# Temp-sensor-RS485.net
KiCad netlist of a schematic drawn in EAGLE
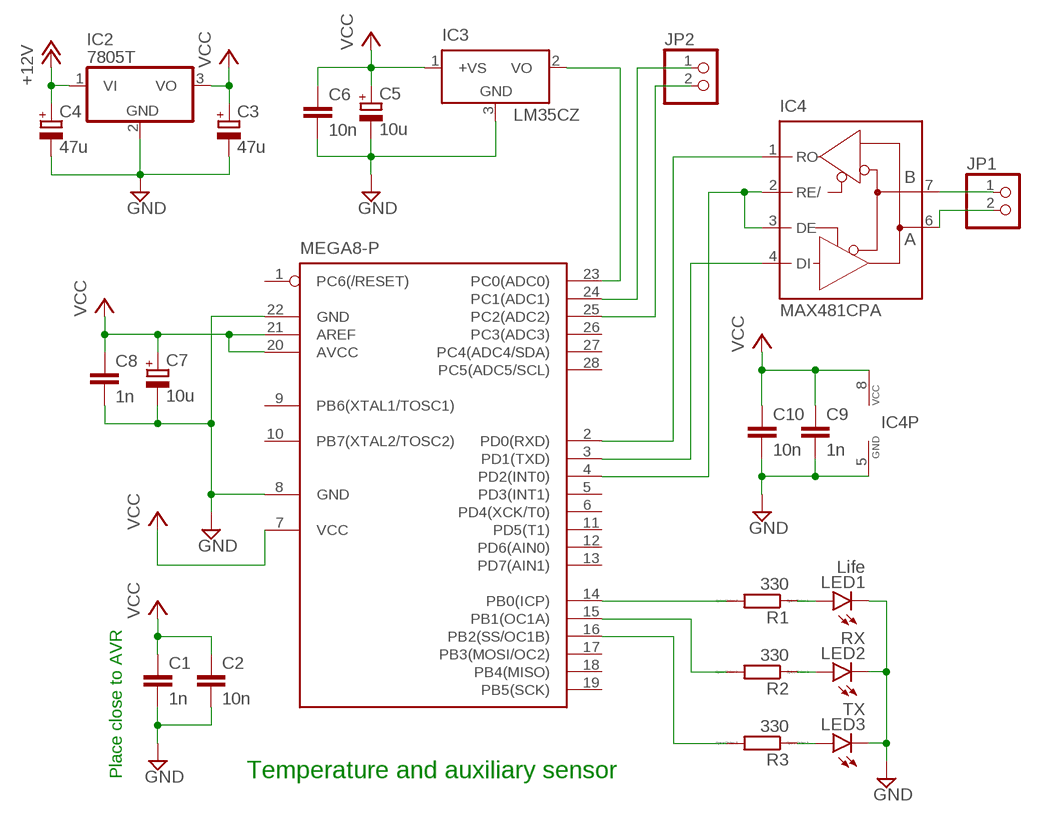
[diagram p0: schematic, sheet 1]

(export (version "E")
  (design (tool "Eeschema 10.0.6"))
  (components
    (comp (ref "C1")
      (value "1n")
      (footprint "eagle-import:C025-024X044")
      (libsource (lib "eagle-import") (part "C-EU025-024X044"))
    )
    (comp (ref "C2")
      (value "10n")
      (footprint "eagle-import:C025-024X044")
      (libsource (lib "eagle-import") (part "C-EU025-024X044"))
    )
    (comp (ref "C3")
      (value "47u")
      (footprint "eagle-import:E1,8-4")
      (libsource (lib "eagle-import") (part "CPOL-EUE1.8-4"))
    )
    (comp (ref "C4")
      (value "47u")
      (footprint "eagle-import:E1,8-4")
      (libsource (lib "eagle-import") (part "CPOL-EUE1.8-4"))
    )
    (comp (ref "C5")
      (value "10u")
      (footprint "eagle-import:E1,8-4")
      (libsource (lib "eagle-import") (part "CPOL-EUE1.8-4"))
    )
    (comp (ref "C6")
      (value "10n")
      (footprint "eagle-import:C025-024X044")
      (libsource (lib "eagle-import") (part "C-EU025-024X044"))
    )
    (comp (ref "C7")
      (value "10u")
      (footprint "eagle-import:E1,8-4")
      (libsource (lib "eagle-import") (part "CPOL-EUE1.8-4"))
    )
    (comp (ref "C8")
      (value "1n")
      (footprint "eagle-import:C025-024X044")
      (libsource (lib "eagle-import") (part "C-EU025-024X044"))
    )
    (comp (ref "C9")
      (value "1n")
      (footprint "eagle-import:C025-024X044")
      (libsource (lib "eagle-import") (part "C-EU025-024X044"))
    )
    (comp (ref "C10")
      (value "10n")
      (footprint "eagle-import:C025-024X044")
      (libsource (lib "eagle-import") (part "C-EU025-024X044"))
    )
    (comp (ref "IC1")
      (value "MEGA8-P")
      (footprint "eagle-import:DIL28-3")
      (libsource (lib "eagle-import") (part "MEGA8-P"))
    )
    (comp (ref "IC2")
      (value "7805T")
      (footprint "eagle-import:TO220H")
      (libsource (lib "eagle-import") (part "78T05"))
    )
    (comp (ref "IC3")
      (value "LM35CZ")
      (footprint "eagle-import:TO92")
      (libsource (lib "eagle-import") (part "LM35CZ"))
    )
    (comp (ref "IC4")
      (value "MAX481CPA")
      (footprint "eagle-import:DIL08")
      (fields (field (name "MPN") "MAX481CPA+"))
      (libsource (lib "eagle-import") (part "MAX481CPA"))
    )
    (comp (ref "JP1")
      (value "PINHD-1X2")
      (footprint "eagle-import:1X02")
      (libsource (lib "eagle-import") (part "PINHD-1X2"))
    )
    (comp (ref "JP2")
      (value "PINHD-1X2")
      (footprint "eagle-import:1X02")
      (libsource (lib "eagle-import") (part "PINHD-1X2"))
    )
    (comp (ref "LED1")
      (value "Life")
      (footprint "eagle-import:LED5MM")
      (libsource (lib "eagle-import") (part "LED5MM"))
    )
    (comp (ref "LED2")
      (value "RX")
      (footprint "eagle-import:LED5MM")
      (libsource (lib "eagle-import") (part "LED5MM"))
    )
    (comp (ref "LED3")
      (value "TX")
      (footprint "eagle-import:LED5MM")
      (libsource (lib "eagle-import") (part "LED5MM"))
    )
    (comp (ref "R1")
      (value "330")
      (footprint "eagle-import:0204_7")
      (libsource (lib "eagle-import") (part "R0204/7"))
    )
    (comp (ref "R2")
      (value "330")
      (footprint "eagle-import:0204_7")
      (libsource (lib "eagle-import") (part "R0204/7"))
    )
    (comp (ref "R3")
      (value "330")
      (footprint "eagle-import:0204_7")
      (libsource (lib "eagle-import") (part "R0204/7"))
    )
  )
  (nets
    (net (code "1") (name "+12V") (class "Default")
      (node (ref "C4") (pin "+") (pinfunction "+_+") (pintype "passive"))
      (node (ref "IC2") (pin "1") (pinfunction "VI_1") (pintype "input"))
    )
    (net (code "2") (name "GND") (class "Default")
      (node (ref "C1") (pin "2") (pinfunction "2_2") (pintype "passive"))
      (node (ref "C10") (pin "2") (pinfunction "2_2") (pintype "passive"))
      (node (ref "C2") (pin "2") (pinfunction "2_2") (pintype "passive"))
      (node (ref "C3") (pin "-") (pinfunction "-_-") (pintype "passive"))
      (node (ref "C4") (pin "-") (pinfunction "-_-") (pintype "passive"))
      (node (ref "C5") (pin "-") (pinfunction "-_-") (pintype "passive"))
      (node (ref "C6") (pin "2") (pinfunction "2_2") (pintype "passive"))
      (node (ref "C7") (pin "-") (pinfunction "-_-") (pintype "passive"))
      (node (ref "C8") (pin "2") (pinfunction "2_2") (pintype "passive"))
      (node (ref "C9") (pin "2") (pinfunction "2_2") (pintype "passive"))
      (node (ref "IC1") (pin "22") (pinfunction "GND_22") (pintype "power_in"))
      (node (ref "IC1") (pin "8") (pinfunction "GND_8") (pintype "power_in"))
      (node (ref "IC2") (pin "2") (pinfunction "GND_2") (pintype "passive"))
      (node (ref "IC3") (pin "3") (pinfunction "GND_3") (pintype "power_in"))
      (node (ref "IC4") (pin "5") (pinfunction "GND_5") (pintype "power_in"))
      (node (ref "LED1") (pin "K") (pinfunction "C_K") (pintype "passive"))
      (node (ref "LED2") (pin "K") (pinfunction "C_K") (pintype "passive"))
      (node (ref "LED3") (pin "K") (pinfunction "C_K") (pintype "passive"))
    )
    (net (code "3") (name "Net-(IC1-PB0(ICP))") (class "Default")
      (node (ref "IC1") (pin "14") (pinfunction "PB0(ICP)_14") (pintype "bidirectional"))
      (node (ref "R1") (pin "2") (pinfunction "2_2") (pintype "passive"))
    )
    (net (code "4") (name "Net-(IC1-PB1(OC1A))") (class "Default")
      (node (ref "IC1") (pin "15") (pinfunction "PB1(OC1A)_15") (pintype "bidirectional"))
      (node (ref "R2") (pin "2") (pinfunction "2_2") (pintype "passive"))
    )
    (net (code "5") (name "Net-(IC1-PB2(SS{slash}OC1B))") (class "Default")
      (node (ref "IC1") (pin "16") (pinfunction "PB2(SS/OC1B)_16") (pintype "bidirectional"))
      (node (ref "R3") (pin "2") (pinfunction "2_2") (pintype "passive"))
    )
    (net (code "6") (name "Net-(IC1-PC0(ADC0))") (class "Default")
      (node (ref "IC1") (pin "23") (pinfunction "PC0(ADC0)_23") (pintype "bidirectional"))
      (node (ref "IC3") (pin "2") (pinfunction "VO_2") (pintype "input"))
    )
    (net (code "7") (name "Net-(IC1-PC1(ADC1))") (class "Default")
      (node (ref "IC1") (pin "24") (pinfunction "PC1(ADC1)_24") (pintype "bidirectional"))
      (node (ref "JP2") (pin "1") (pinfunction "1_1") (pintype "passive"))
    )
    (net (code "8") (name "Net-(IC1-PC2(ADC2))") (class "Default")
      (node (ref "IC1") (pin "25") (pinfunction "PC2(ADC2)_25") (pintype "bidirectional"))
      (node (ref "JP2") (pin "2") (pinfunction "2_2") (pintype "passive"))
    )
    (net (code "9") (name "Net-(IC1-PD0(RXD))") (class "Default")
      (node (ref "IC1") (pin "2") (pinfunction "PD0(RXD)_2") (pintype "bidirectional"))
      (node (ref "IC4") (pin "1") (pinfunction "RO_1") (pintype "output"))
    )
    (net (code "10") (name "Net-(IC1-PD1(TXD))") (class "Default")
      (node (ref "IC1") (pin "3") (pinfunction "PD1(TXD)_3") (pintype "bidirectional"))
      (node (ref "IC4") (pin "4") (pinfunction "DI_4") (pintype "input"))
    )
    (net (code "11") (name "Net-(IC1-PD2(INT0))") (class "Default")
      (node (ref "IC1") (pin "4") (pinfunction "PD2(INT0)_4") (pintype "bidirectional"))
      (node (ref "IC4") (pin "2") (pinfunction "RE/_2") (pintype "input"))
      (node (ref "IC4") (pin "3") (pinfunction "DE_3") (pintype "input"))
    )
    (net (code "12") (name "Net-(IC4A-A)") (class "Default")
      (node (ref "IC4") (pin "6") (pinfunction "A_6") (pintype "passive"))
      (node (ref "JP1") (pin "2") (pinfunction "2_2") (pintype "passive"))
    )
    (net (code "13") (name "Net-(IC4A-B)") (class "Default")
      (node (ref "IC4") (pin "7") (pinfunction "B_7") (pintype "passive"))
      (node (ref "JP1") (pin "1") (pinfunction "1_1") (pintype "passive"))
    )
    (net (code "14") (name "Net-(LED1-PadA)") (class "Default")
      (node (ref "LED1") (pin "A") (pinfunction "A_A") (pintype "passive"))
      (node (ref "R1") (pin "1") (pinfunction "1_1") (pintype "passive"))
    )
    (net (code "15") (name "Net-(LED2-PadA)") (class "Default")
      (node (ref "LED2") (pin "A") (pinfunction "A_A") (pintype "passive"))
      (node (ref "R2") (pin "1") (pinfunction "1_1") (pintype "passive"))
    )
    (net (code "16") (name "Net-(LED3-PadA)") (class "Default")
      (node (ref "LED3") (pin "A") (pinfunction "A_A") (pintype "passive"))
      (node (ref "R3") (pin "1") (pinfunction "1_1") (pintype "passive"))
    )
    (net (code "17") (name "VCC") (class "Default")
      (node (ref "C1") (pin "1") (pinfunction "1_1") (pintype "passive"))
      (node (ref "C10") (pin "1") (pinfunction "1_1") (pintype "passive"))
      (node (ref "C2") (pin "1") (pinfunction "1_1") (pintype "passive"))
      (node (ref "C3") (pin "+") (pinfunction "+_+") (pintype "passive"))
      (node (ref "C5") (pin "+") (pinfunction "+_+") (pintype "passive"))
      (node (ref "C6") (pin "1") (pinfunction "1_1") (pintype "passive"))
      (node (ref "C7") (pin "+") (pinfunction "+_+") (pintype "passive"))
      (node (ref "C8") (pin "1") (pinfunction "1_1") (pintype "passive"))
      (node (ref "C9") (pin "1") (pinfunction "1_1") (pintype "passive"))
      (node (ref "IC1") (pin "20") (pinfunction "AVCC_20") (pintype "power_in"))
      (node (ref "IC1") (pin "21") (pinfunction "AREF_21") (pintype "passive"))
      (node (ref "IC1") (pin "7") (pinfunction "VCC_7") (pintype "power_in"))
      (node (ref "IC2") (pin "3") (pinfunction "VO_3") (pintype "passive"))
      (node (ref "IC3") (pin "1") (pinfunction "+VS_1") (pintype "input"))
      (node (ref "IC4") (pin "8") (pinfunction "VCC_8") (pintype "power_in"))
    )
    (net (code "18") (name "unconnected-(IC1-PB3(MOSI{slash}OC2)-Pad17)") (class "Default")
      (node (ref "IC1") (pin "17") (pinfunction "PB3(MOSI/OC2)_17") (pintype "bidirectional"))
    )
    (net (code "19") (name "unconnected-(IC1-PB4(MISO)-Pad18)") (class "Default")
      (node (ref "IC1") (pin "18") (pinfunction "PB4(MISO)_18") (pintype "bidirectional"))
    )
    (net (code "20") (name "unconnected-(IC1-PB5(SCK)-Pad19)") (class "Default")
      (node (ref "IC1") (pin "19") (pinfunction "PB5(SCK)_19") (pintype "bidirectional"))
    )
    (net (code "21") (name "unconnected-(IC1-PB6(XTAL1{slash}TOSC1)-Pad9)") (class "Default")
      (node (ref "IC1") (pin "9") (pinfunction "PB6(XTAL1/TOSC1)_9") (pintype "bidirectional"))
    )
    (net (code "22") (name "unconnected-(IC1-PB7(XTAL2{slash}TOSC2)-Pad10)") (class "Default")
      (node (ref "IC1") (pin "10") (pinfunction "PB7(XTAL2/TOSC2)_10") (pintype "bidirectional"))
    )
    (net (code "23") (name "unconnected-(IC1-PC3(ADC3)-Pad26)") (class "Default")
      (node (ref "IC1") (pin "26") (pinfunction "PC3(ADC3)_26") (pintype "bidirectional"))
    )
    (net (code "24") (name "unconnected-(IC1-PC4(ADC4{slash}SDA)-Pad27)") (class "Default")
      (node (ref "IC1") (pin "27") (pinfunction "PC4(ADC4/SDA)_27") (pintype "bidirectional"))
    )
    (net (code "25") (name "unconnected-(IC1-PC5(ADC5{slash}SCL)-Pad28)") (class "Default")
      (node (ref "IC1") (pin "28") (pinfunction "PC5(ADC5/SCL)_28") (pintype "bidirectional"))
    )
    (net (code "26") (name "unconnected-(IC1-PC6({slash}RESET)-Pad1)") (class "Default")
      (node (ref "IC1") (pin "1") (pinfunction "PC6(/RESET)_1") (pintype "bidirectional"))
    )
    (net (code "27") (name "unconnected-(IC1-PD3(INT1)-Pad5)") (class "Default")
      (node (ref "IC1") (pin "5") (pinfunction "PD3(INT1)_5") (pintype "bidirectional"))
    )
    (net (code "28") (name "unconnected-(IC1-PD4(XCK{slash}T0)-Pad6)") (class "Default")
      (node (ref "IC1") (pin "6") (pinfunction "PD4(XCK/T0)_6") (pintype "bidirectional"))
    )
    (net (code "29") (name "unconnected-(IC1-PD5(T1)-Pad11)") (class "Default")
      (node (ref "IC1") (pin "11") (pinfunction "PD5(T1)_11") (pintype "bidirectional"))
    )
    (net (code "30") (name "unconnected-(IC1-PD6(AIN0)-Pad12)") (class "Default")
      (node (ref "IC1") (pin "12") (pinfunction "PD6(AIN0)_12") (pintype "bidirectional"))
    )
    (net (code "31") (name "unconnected-(IC1-PD7(AIN1)-Pad13)") (class "Default")
      (node (ref "IC1") (pin "13") (pinfunction "PD7(AIN1)_13") (pintype "bidirectional"))
    )
  )
)
